# 1-Schematic_PI_Attenuator_SMD.net
KiCad netlist of a schematic drawn in EasyEDA
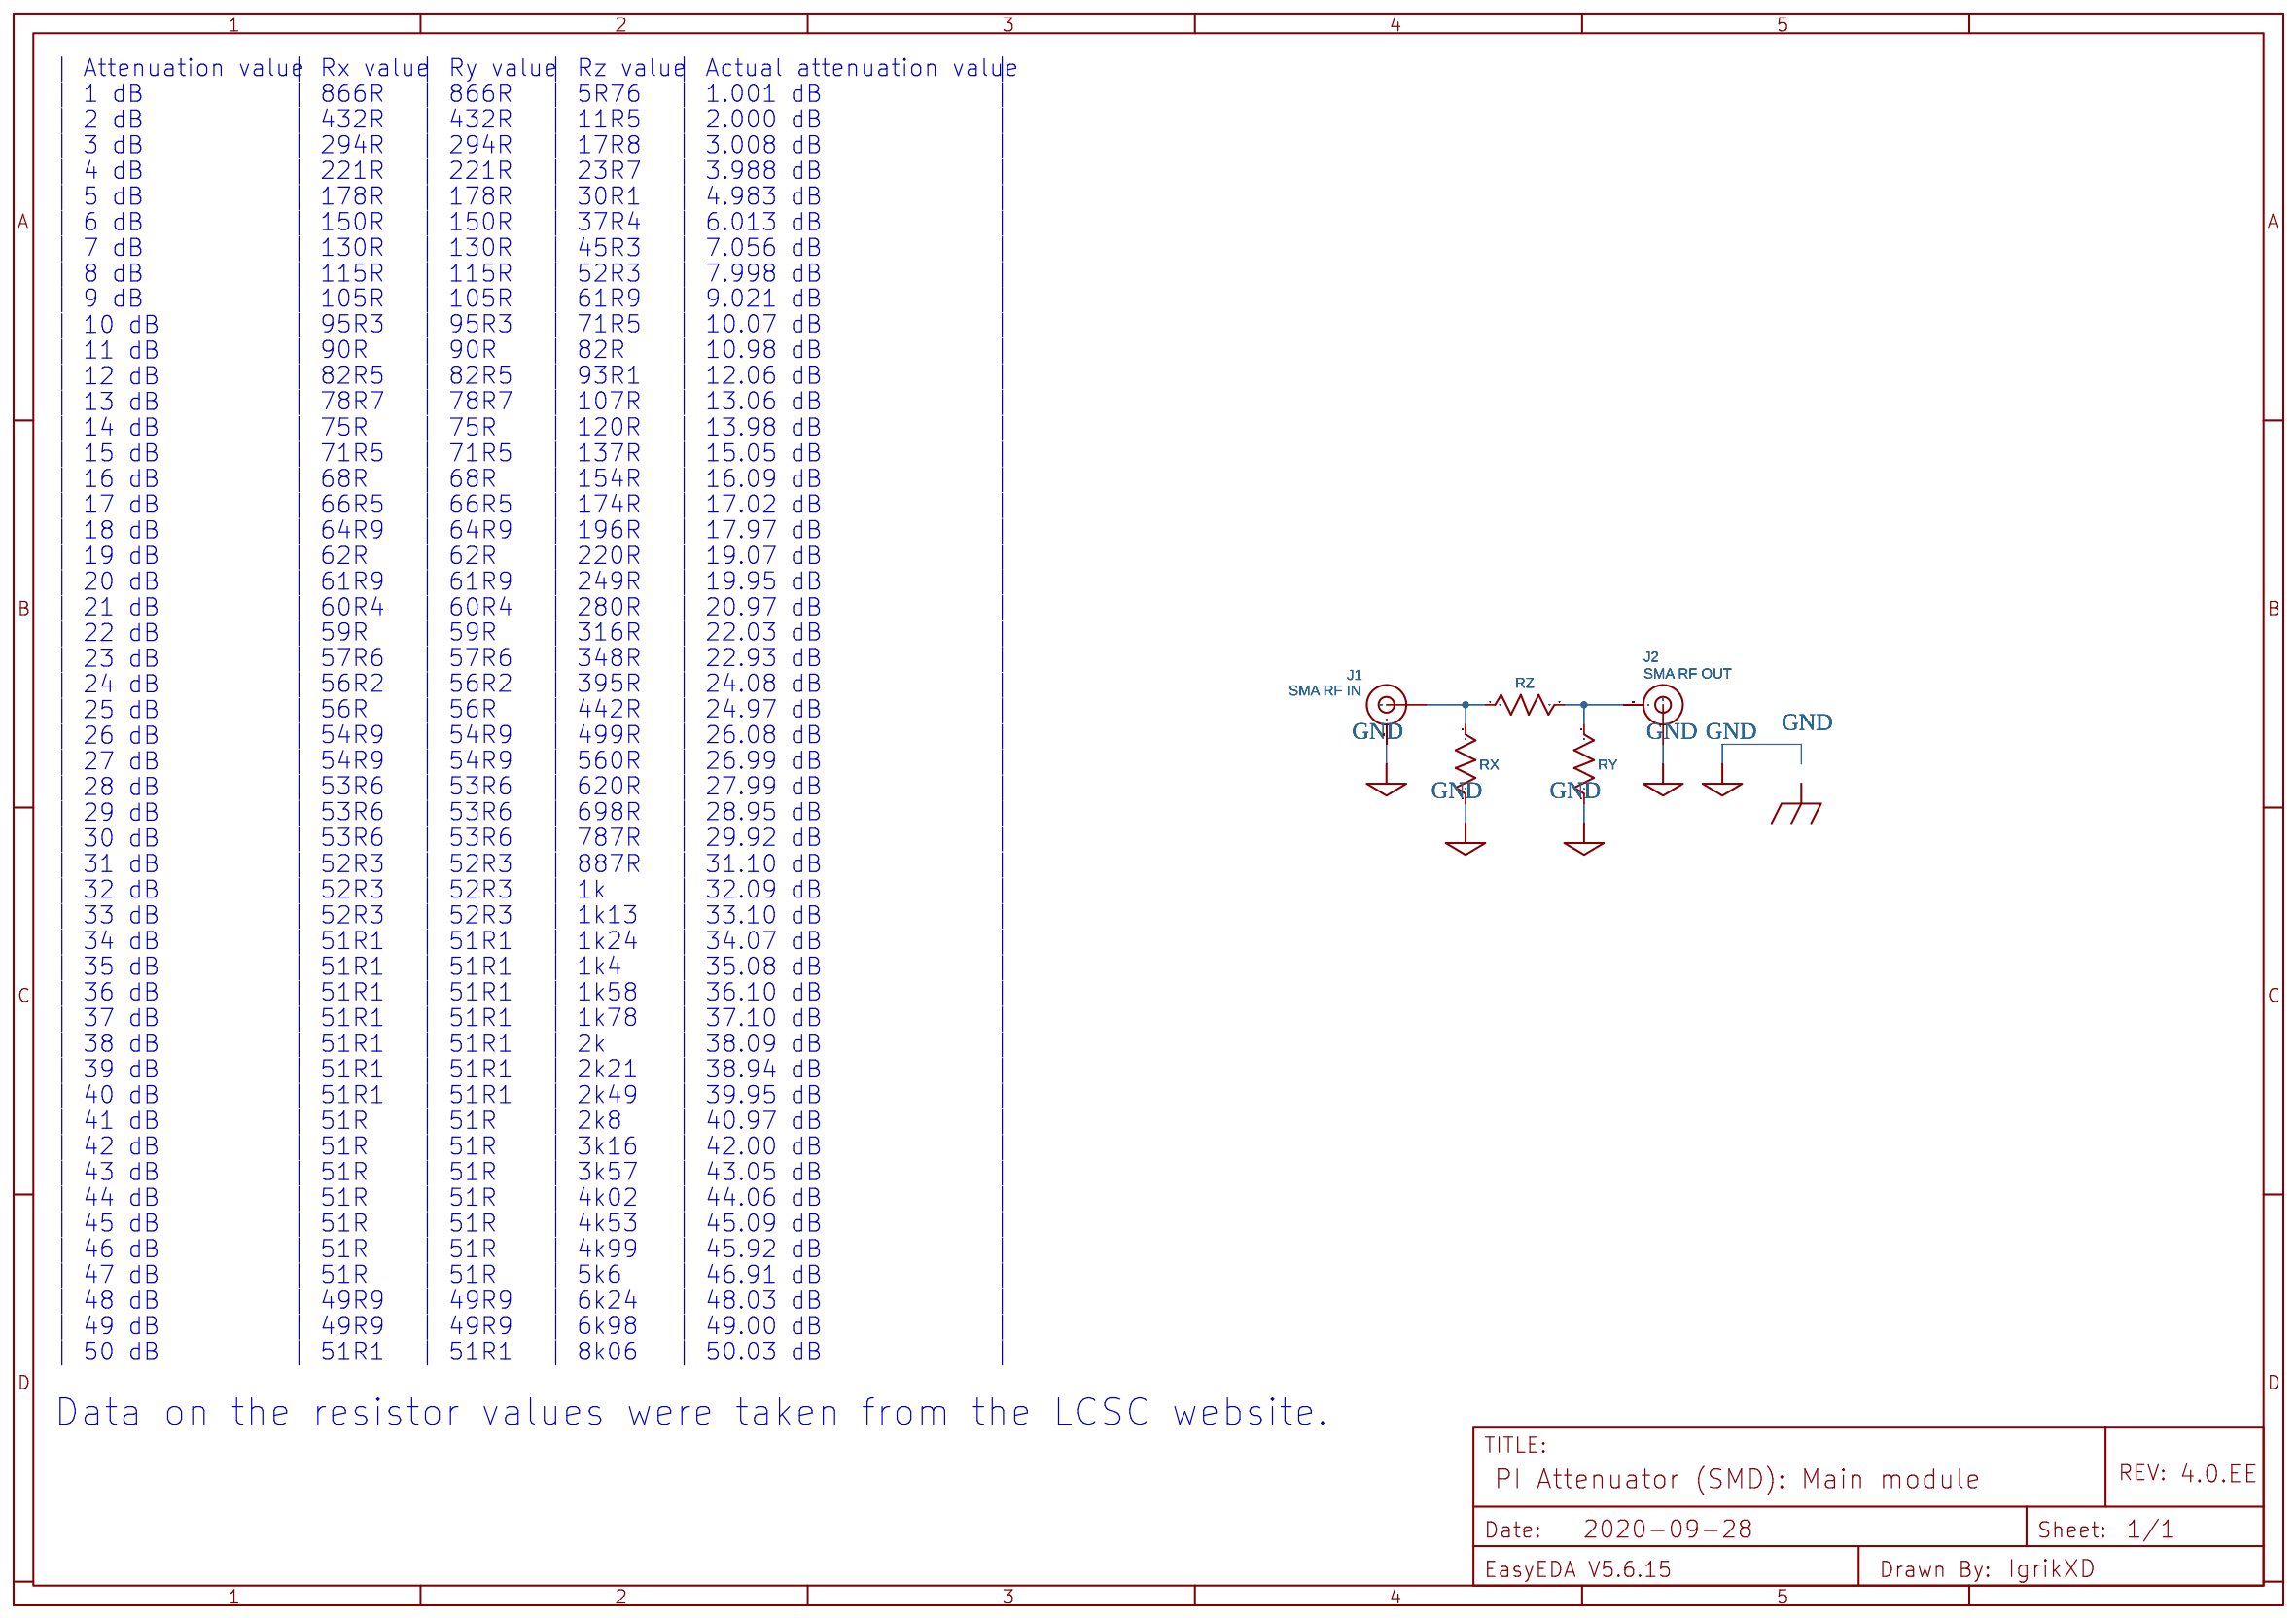
[diagram p0: schematic sheet]

(export (version "E")
  (design (tool "Eeschema 10.0.6"))
  (components
    (comp (ref "J1")
      (value "SMA RF IN")
      (fields
        (field (name "BOM_Manufacturer Part") "ANKX01.0093")
        (field (name "BOM_Supplier Part") "C129604")
      )
      (libsource (lib "") (part "Unknown_700_370"))
    )
    (comp (ref "J2")
      (value "SMA RF OUT")
      (fields
        (field (name "BOM_Manufacturer Part") "ANKX01.0093")
        (field (name "BOM_Supplier Part") "C129604")
      )
      (libsource (lib "") (part "Unknown_815_355"))
    )
    (comp (ref "RX")
      (value "CALCULATED")
      (fields (field (name "BOM_Manufacturer Part") "NULL"))
      (libsource (lib "") (part "Res_0805(1/8W)_US_1"))
    )
    (comp (ref "RY")
      (value "CALCULATED")
      (fields (field (name "BOM_Manufacturer Part") "NULL"))
      (libsource (lib "") (part "Res_0805(1/8W)_US_2"))
    )
    (comp (ref "RZ")
      (value "CALCULATED")
      (fields (field (name "BOM_Manufacturer Part") "NULL"))
      (libsource (lib "") (part "Res_0805(1/8W)_US"))
    )
  )
  (nets
    (net (code "1") (name "GND") (class "Default")
      (node (ref "J1") (pin "GND@0") (pinfunction "GND_GND@0") (pintype "unspecified"))
      (node (ref "J1") (pin "GND@1") (pinfunction "GND_GND@1") (pintype "unspecified"))
      (node (ref "J1") (pin "GND@2") (pinfunction "GND_GND@2") (pintype "unspecified"))
      (node (ref "J1") (pin "GND@3") (pinfunction "GND_GND@3") (pintype "unspecified"))
      (node (ref "J2") (pin "SIG") (pinfunction "SIGNAL_SIG") (pintype "unspecified"))
      (node (ref "RX") (pin "1") (pinfunction "1_1") (pintype "unspecified"))
      (node (ref "RY") (pin "1") (pinfunction "1_1") (pintype "unspecified"))
    )
    (net (code "2") (name "Net-(J1-SIGNAL)") (class "Default")
      (node (ref "J1") (pin "SIG") (pinfunction "SIGNAL_SIG") (pintype "unspecified"))
      (node (ref "RX") (pin "2") (pinfunction "2_2") (pintype "unspecified"))
      (node (ref "RZ") (pin "1") (pinfunction "1_1") (pintype "unspecified"))
    )
    (net (code "3") (name "Net-(J2-GND-PadGND@0)") (class "Default")
      (node (ref "J2") (pin "GND@0") (pinfunction "GND_GND@0") (pintype "unspecified"))
      (node (ref "J2") (pin "GND@1") (pinfunction "GND_GND@1") (pintype "unspecified"))
      (node (ref "J2") (pin "GND@2") (pinfunction "GND_GND@2") (pintype "unspecified"))
      (node (ref "J2") (pin "GND@3") (pinfunction "GND_GND@3") (pintype "unspecified"))
      (node (ref "RY") (pin "2") (pinfunction "2_2") (pintype "unspecified"))
      (node (ref "RZ") (pin "2") (pinfunction "2_2") (pintype "unspecified"))
    )
  )
)
